# HzMF_Odrive.net
KiCad netlist of a schematic drawn in Altium Designer
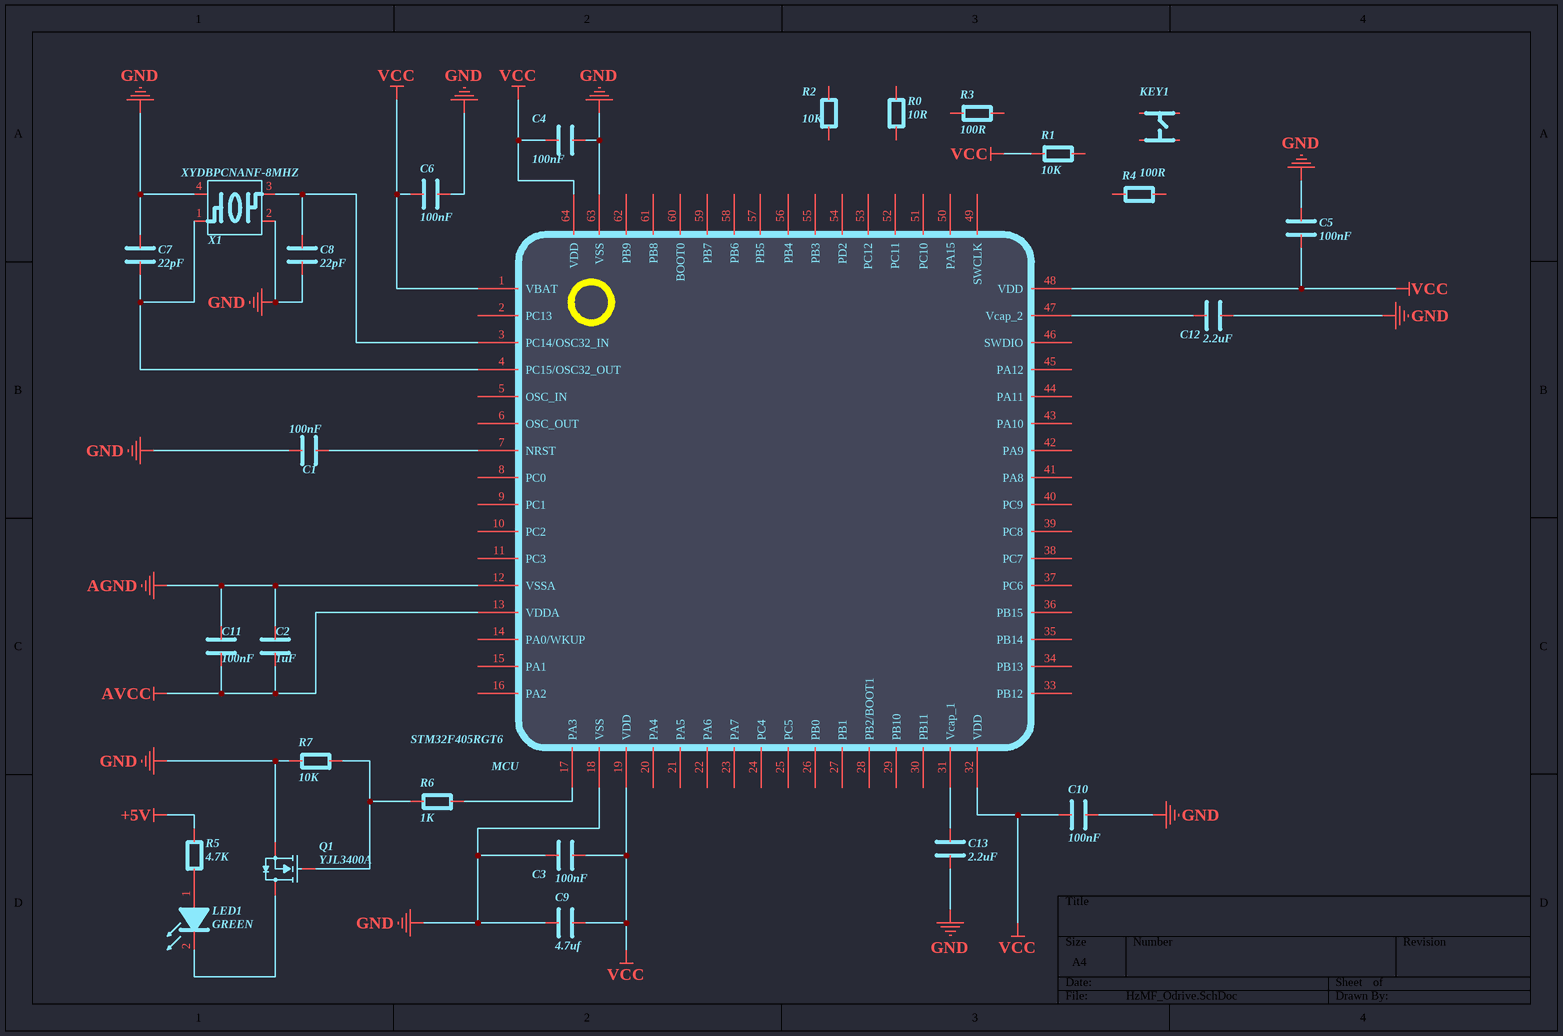
[diagram p0: HzMF_Odrive.SchDoc]

(export (version "E")
  (design (tool "Eeschema 10.0.6"))
  (components
    (comp (ref "C1")
      (value "100nF")
      (footprint "CAP_0603")
      (libsource (lib "HZMF_Private_Library") (part "C"))
    )
    (comp (ref "C2")
      (value "1uF")
      (footprint "CAP_0603")
      (description "电容")
      (libsource (lib "HZMF_Private_Library") (part "C"))
    )
    (comp (ref "C3")
      (value "100nF")
      (footprint "CAP_0603")
      (description "电容")
      (libsource (lib "HZMF_Private_Library") (part "C"))
    )
    (comp (ref "C4")
      (value "100nF")
      (footprint "CAP_0603")
      (description "电容")
      (libsource (lib "HZMF_Private_Library") (part "C"))
    )
    (comp (ref "C5")
      (value "100nF")
      (footprint "CAP_0603")
      (description "电容")
      (libsource (lib "HZMF_Private_Library") (part "C"))
    )
    (comp (ref "C6")
      (value "100nF")
      (footprint "CAP_0603")
      (description "电容")
      (libsource (lib "HZMF_Private_Library") (part "C"))
    )
    (comp (ref "C7")
      (value "22pF")
      (footprint "CAP_0603")
      (description "电容")
      (libsource (lib "HZMF_Private_Library") (part "C"))
    )
    (comp (ref "C8")
      (value "22pF")
      (footprint "CAP_0603")
      (description "电容")
      (libsource (lib "HZMF_Private_Library") (part "C"))
    )
    (comp (ref "C9")
      (value "4.7uf")
      (footprint "CAP_0603")
      (description "电容")
      (libsource (lib "HZMF_Private_Library") (part "C"))
    )
    (comp (ref "C10")
      (value "100nF")
      (footprint "CAP_0603")
      (description "电容")
      (libsource (lib "HZMF_Private_Library") (part "C"))
    )
    (comp (ref "C11")
      (value "100nF")
      (footprint "CAP_0603")
      (description "电容")
      (libsource (lib "HZMF_Private_Library") (part "C"))
    )
    (comp (ref "C12")
      (value "2.2uF")
      (footprint "CAP_0603")
      (description "电容")
      (libsource (lib "HZMF_Private_Library") (part "C"))
    )
    (comp (ref "C13")
      (value "2.2uF")
      (footprint "CAP_0603")
      (description "电容")
      (libsource (lib "HZMF_Private_Library") (part "C"))
    )
    (comp (ref "KEY1")
      (value "K1")
      (footprint "KEY-SMD_4P-L6.0-W6.0-P4.50-LS10.0")
      (description "Button")
      (libsource (lib "HZMF_Private_Library") (part "Button_4P"))
    )
    (comp (ref "LED1")
      (value "GREEN")
      (footprint "LED_green")
      (description "LED灯")
      (libsource (lib "HZMF_Private_Library") (part "LED"))
    )
    (comp (ref "MCU")
      (value "STM32F405RGT6")
      (footprint "LQFP_64")
      (description "STM32F4")
      (libsource (lib "HZMF_Private_Library") (part "STM32F405RGT6"))
    )
    (comp (ref "Q1")
      (value "YJL3400A")
      (footprint "SOT23_3")
      (description "N_MOS")
      (libsource (lib "HZMF_Private_Library") (part "MOSFET_N"))
    )
    (comp (ref "R0")
      (value "10R")
      (footprint "RES_0603")
      (description "电阻")
      (libsource (lib "HZMF_Private_Library") (part "R"))
    )
    (comp (ref "R1") (value "10K") (footprint "RES_0603") (libsource (lib "HZMF_Private_Library") (part "R")))
    (comp (ref "R2")
      (value "10K")
      (footprint "RES_0603")
      (description "电阻")
      (libsource (lib "HZMF_Private_Library") (part "R"))
    )
    (comp (ref "R3")
      (value "100R")
      (footprint "RES_0603")
      (description "电阻")
      (libsource (lib "HZMF_Private_Library") (part "R"))
    )
    (comp (ref "R4")
      (value "100R")
      (footprint "RES_0603")
      (description "电阻")
      (libsource (lib "HZMF_Private_Library") (part "R"))
    )
    (comp (ref "R5")
      (value "4.7K")
      (footprint "RES_0603")
      (description "电阻")
      (libsource (lib "HZMF_Private_Library") (part "R"))
    )
    (comp (ref "R6")
      (value "1K")
      (footprint "RES_0603")
      (description "电阻")
      (libsource (lib "HZMF_Private_Library") (part "R"))
    )
    (comp (ref "R7")
      (value "10K")
      (footprint "RES_0603")
      (description "电阻")
      (libsource (lib "HZMF_Private_Library") (part "R"))
    )
    (comp (ref "X1")
      (value "XYDBPCNANF-8MHZ")
      (footprint "CARSTAL_4P_2520")
      (description "四脚无源晶振")
      (fields
        (field (name "MANUFACTURER") "TAITIEN(泰艺电子)")
        (field (name "MANUFACTURER PART") "XYDBPCNANF-12MHZ")
      )
      (libsource (lib "HZMF_Private_Library") (part "Crystal_4P"))
    )
  )
  (nets
    (net (code "1") (name "+5V") (class "Default")
      (node (ref "R5") (pin "1") (pinfunction "1_1") (pintype "passive"))
    )
    (net (code "2") (name "AGND") (class "Default")
      (node (ref "C11") (pin "1") (pinfunction "1_1") (pintype "passive"))
      (node (ref "C2") (pin "1") (pinfunction "1_1") (pintype "passive"))
      (node (ref "MCU") (pin "12") (pinfunction "VSSA_12") (pintype "passive"))
    )
    (net (code "3") (name "AVCC") (class "Default")
      (node (ref "C11") (pin "2") (pinfunction "2_2") (pintype "passive"))
      (node (ref "C2") (pin "2") (pinfunction "2_2") (pintype "passive"))
      (node (ref "MCU") (pin "13") (pinfunction "VDDA_13") (pintype "passive"))
    )
    (net (code "4") (name "GND") (class "Default")
      (node (ref "C1") (pin "2") (pinfunction "2_2") (pintype "passive"))
      (node (ref "C10") (pin "1") (pinfunction "1_1") (pintype "passive"))
      (node (ref "C12") (pin "2") (pinfunction "2_2") (pintype "passive"))
      (node (ref "C13") (pin "2") (pinfunction "2_2") (pintype "passive"))
      (node (ref "C3") (pin "1") (pinfunction "1_1") (pintype "passive"))
      (node (ref "C4") (pin "2") (pinfunction "2_2") (pintype "passive"))
      (node (ref "C5") (pin "1") (pinfunction "1_1") (pintype "passive"))
      (node (ref "C6") (pin "1") (pinfunction "1_1") (pintype "passive"))
      (node (ref "C7") (pin "1") (pinfunction "1_1") (pintype "passive"))
      (node (ref "C8") (pin "2") (pinfunction "2_2") (pintype "passive"))
      (node (ref "C9") (pin "1") (pinfunction "1_1") (pintype "passive"))
      (node (ref "MCU") (pin "18") (pinfunction "VSS_18") (pintype "passive"))
      (node (ref "MCU") (pin "63") (pinfunction "VSS_63") (pintype "passive"))
      (node (ref "Q1") (pin "2") (pinfunction "S_2") (pintype "passive"))
      (node (ref "R7") (pin "1") (pinfunction "1_1") (pintype "passive"))
      (node (ref "X1") (pin "2") (pinfunction "GND_2") (pintype "passive"))
      (node (ref "X1") (pin "4") (pinfunction "GND_4") (pintype "passive"))
    )
    (net (code "5") (name "Net-(LED1-+)") (class "Default")
      (node (ref "LED1") (pin "1") (pinfunction "+_1") (pintype "passive"))
      (node (ref "R5") (pin "2") (pinfunction "2_2") (pintype "passive"))
    )
    (net (code "6") (name "Net-(LED1--)") (class "Default")
      (node (ref "LED1") (pin "2") (pinfunction "-_2") (pintype "passive"))
      (node (ref "Q1") (pin "3") (pinfunction "D_3") (pintype "passive"))
    )
    (net (code "7") (name "Net-(MCU-NRST)") (class "Default")
      (node (ref "C1") (pin "1") (pinfunction "1_1") (pintype "passive"))
      (node (ref "MCU") (pin "7") (pinfunction "NRST_7") (pintype "passive"))
    )
    (net (code "8") (name "Net-(MCU-PA3)") (class "Default")
      (node (ref "MCU") (pin "17") (pinfunction "PA3_17") (pintype "passive"))
      (node (ref "R6") (pin "2") (pinfunction "2_2") (pintype "passive"))
    )
    (net (code "9") (name "Net-(MCU-PC14{slash}OSC32_IN)") (class "Default")
      (node (ref "C8") (pin "1") (pinfunction "1_1") (pintype "passive"))
      (node (ref "MCU") (pin "3") (pinfunction "PC14/OSC32_IN_3") (pintype "passive"))
      (node (ref "X1") (pin "3") (pinfunction "3_3") (pintype "passive"))
    )
    (net (code "10") (name "Net-(MCU-PC15{slash}OSC32_OUT)") (class "Default")
      (node (ref "C7") (pin "2") (pinfunction "2_2") (pintype "passive"))
      (node (ref "MCU") (pin "4") (pinfunction "PC15/OSC32_OUT_4") (pintype "passive"))
      (node (ref "X1") (pin "1") (pinfunction "1_1") (pintype "passive"))
    )
    (net (code "11") (name "Net-(MCU-Vcap_1)") (class "Default")
      (node (ref "C13") (pin "1") (pinfunction "1_1") (pintype "passive"))
      (node (ref "MCU") (pin "31") (pinfunction "Vcap_1_31") (pintype "passive"))
    )
    (net (code "12") (name "Net-(MCU-Vcap_2)") (class "Default")
      (node (ref "C12") (pin "1") (pinfunction "1_1") (pintype "passive"))
      (node (ref "MCU") (pin "47") (pinfunction "Vcap_2_47") (pintype "passive"))
    )
    (net (code "13") (name "Net-(Q1-G)") (class "Default")
      (node (ref "Q1") (pin "1") (pinfunction "G_1") (pintype "passive"))
      (node (ref "R6") (pin "1") (pinfunction "1_1") (pintype "passive"))
      (node (ref "R7") (pin "2") (pinfunction "2_2") (pintype "passive"))
    )
    (net (code "14") (name "VCC") (class "Default")
      (node (ref "C10") (pin "2") (pinfunction "2_2") (pintype "passive"))
      (node (ref "C3") (pin "2") (pinfunction "2_2") (pintype "passive"))
      (node (ref "C4") (pin "1") (pinfunction "1_1") (pintype "passive"))
      (node (ref "C5") (pin "2") (pinfunction "2_2") (pintype "passive"))
      (node (ref "C6") (pin "2") (pinfunction "2_2") (pintype "passive"))
      (node (ref "C9") (pin "2") (pinfunction "2_2") (pintype "passive"))
      (node (ref "MCU") (pin "1") (pinfunction "VBAT_1") (pintype "passive"))
      (node (ref "MCU") (pin "19") (pinfunction "VDD_19") (pintype "passive"))
      (node (ref "MCU") (pin "32") (pinfunction "VDD_32") (pintype "passive"))
      (node (ref "MCU") (pin "48") (pinfunction "VDD_48") (pintype "passive"))
      (node (ref "MCU") (pin "64") (pinfunction "VDD_64") (pintype "passive"))
      (node (ref "R1") (pin "2") (pinfunction "2_2") (pintype "passive"))
    )
    (net (code "15") (name "unconnected-(KEY1-Pad1)") (class "Default")
      (node (ref "KEY1") (pin "1") (pinfunction "1_1") (pintype "passive"))
    )
    (net (code "16") (name "unconnected-(KEY1-Pad2)") (class "Default")
      (node (ref "KEY1") (pin "2") (pinfunction "2_2") (pintype "passive"))
    )
    (net (code "17") (name "unconnected-(KEY1-Pad3)") (class "Default")
      (node (ref "KEY1") (pin "3") (pinfunction "3_3") (pintype "passive"))
    )
    (net (code "18") (name "unconnected-(KEY1-Pad4)") (class "Default")
      (node (ref "KEY1") (pin "4") (pinfunction "4_4") (pintype "passive"))
    )
    (net (code "19") (name "unconnected-(MCU-BOOT0-Pad60)") (class "Default")
      (node (ref "MCU") (pin "60") (pinfunction "BOOT0_60") (pintype "passive"))
    )
    (net (code "20") (name "unconnected-(MCU-OSC_IN-Pad5)") (class "Default")
      (node (ref "MCU") (pin "5") (pinfunction "OSC_IN_5") (pintype "passive"))
    )
    (net (code "21") (name "unconnected-(MCU-OSC_OUT-Pad6)") (class "Default")
      (node (ref "MCU") (pin "6") (pinfunction "OSC_OUT_6") (pintype "passive"))
    )
    (net (code "22") (name "unconnected-(MCU-PA0{slash}WKUP-Pad14)") (class "Default")
      (node (ref "MCU") (pin "14") (pinfunction "PA0/WKUP_14") (pintype "passive"))
    )
    (net (code "23") (name "unconnected-(MCU-PA1-Pad15)") (class "Default")
      (node (ref "MCU") (pin "15") (pinfunction "PA1_15") (pintype "passive"))
    )
    (net (code "24") (name "unconnected-(MCU-PA2-Pad16)") (class "Default")
      (node (ref "MCU") (pin "16") (pinfunction "PA2_16") (pintype "passive"))
    )
    (net (code "25") (name "unconnected-(MCU-PA4-Pad20)") (class "Default")
      (node (ref "MCU") (pin "20") (pinfunction "PA4_20") (pintype "passive"))
    )
    (net (code "26") (name "unconnected-(MCU-PA5-Pad21)") (class "Default")
      (node (ref "MCU") (pin "21") (pinfunction "PA5_21") (pintype "passive"))
    )
    (net (code "27") (name "unconnected-(MCU-PA6-Pad22)") (class "Default")
      (node (ref "MCU") (pin "22") (pinfunction "PA6_22") (pintype "passive"))
    )
    (net (code "28") (name "unconnected-(MCU-PA7-Pad23)") (class "Default")
      (node (ref "MCU") (pin "23") (pinfunction "PA7_23") (pintype "passive"))
    )
    (net (code "29") (name "unconnected-(MCU-PA8-Pad41)") (class "Default")
      (node (ref "MCU") (pin "41") (pinfunction "PA8_41") (pintype "passive"))
    )
    (net (code "30") (name "unconnected-(MCU-PA9-Pad42)") (class "Default")
      (node (ref "MCU") (pin "42") (pinfunction "PA9_42") (pintype "passive"))
    )
    (net (code "31") (name "unconnected-(MCU-PA10-Pad43)") (class "Default")
      (node (ref "MCU") (pin "43") (pinfunction "PA10_43") (pintype "passive"))
    )
    (net (code "32") (name "unconnected-(MCU-PA11-Pad44)") (class "Default")
      (node (ref "MCU") (pin "44") (pinfunction "PA11_44") (pintype "passive"))
    )
    (net (code "33") (name "unconnected-(MCU-PA12-Pad45)") (class "Default")
      (node (ref "MCU") (pin "45") (pinfunction "PA12_45") (pintype "passive"))
    )
    (net (code "34") (name "unconnected-(MCU-PA15-Pad50)") (class "Default")
      (node (ref "MCU") (pin "50") (pinfunction "PA15_50") (pintype "passive"))
    )
    (net (code "35") (name "unconnected-(MCU-PB0-Pad26)") (class "Default")
      (node (ref "MCU") (pin "26") (pinfunction "PB0_26") (pintype "passive"))
    )
    (net (code "36") (name "unconnected-(MCU-PB1-Pad27)") (class "Default")
      (node (ref "MCU") (pin "27") (pinfunction "PB1_27") (pintype "passive"))
    )
    (net (code "37") (name "unconnected-(MCU-PB2{slash}BOOT1-Pad28)") (class "Default")
      (node (ref "MCU") (pin "28") (pinfunction "PB2/BOOT1_28") (pintype "passive"))
    )
    (net (code "38") (name "unconnected-(MCU-PB3-Pad55)") (class "Default")
      (node (ref "MCU") (pin "55") (pinfunction "PB3_55") (pintype "passive"))
    )
    (net (code "39") (name "unconnected-(MCU-PB4-Pad56)") (class "Default")
      (node (ref "MCU") (pin "56") (pinfunction "PB4_56") (pintype "passive"))
    )
    (net (code "40") (name "unconnected-(MCU-PB5-Pad57)") (class "Default")
      (node (ref "MCU") (pin "57") (pinfunction "PB5_57") (pintype "passive"))
    )
    (net (code "41") (name "unconnected-(MCU-PB6-Pad58)") (class "Default")
      (node (ref "MCU") (pin "58") (pinfunction "PB6_58") (pintype "passive"))
    )
    (net (code "42") (name "unconnected-(MCU-PB7-Pad59)") (class "Default")
      (node (ref "MCU") (pin "59") (pinfunction "PB7_59") (pintype "passive"))
    )
    (net (code "43") (name "unconnected-(MCU-PB8-Pad61)") (class "Default")
      (node (ref "MCU") (pin "61") (pinfunction "PB8_61") (pintype "passive"))
    )
    (net (code "44") (name "unconnected-(MCU-PB9-Pad62)") (class "Default")
      (node (ref "MCU") (pin "62") (pinfunction "PB9_62") (pintype "passive"))
    )
    (net (code "45") (name "unconnected-(MCU-PB10-Pad29)") (class "Default")
      (node (ref "MCU") (pin "29") (pinfunction "PB10_29") (pintype "passive"))
    )
    (net (code "46") (name "unconnected-(MCU-PB11-Pad30)") (class "Default")
      (node (ref "MCU") (pin "30") (pinfunction "PB11_30") (pintype "passive"))
    )
    (net (code "47") (name "unconnected-(MCU-PB12-Pad33)") (class "Default")
      (node (ref "MCU") (pin "33") (pinfunction "PB12_33") (pintype "passive"))
    )
    (net (code "48") (name "unconnected-(MCU-PB13-Pad34)") (class "Default")
      (node (ref "MCU") (pin "34") (pinfunction "PB13_34") (pintype "passive"))
    )
    (net (code "49") (name "unconnected-(MCU-PB14-Pad35)") (class "Default")
      (node (ref "MCU") (pin "35") (pinfunction "PB14_35") (pintype "passive"))
    )
    (net (code "50") (name "unconnected-(MCU-PB15-Pad36)") (class "Default")
      (node (ref "MCU") (pin "36") (pinfunction "PB15_36") (pintype "passive"))
    )
    (net (code "51") (name "unconnected-(MCU-PC0-Pad8)") (class "Default")
      (node (ref "MCU") (pin "8") (pinfunction "PC0_8") (pintype "passive"))
    )
    (net (code "52") (name "unconnected-(MCU-PC1-Pad9)") (class "Default")
      (node (ref "MCU") (pin "9") (pinfunction "PC1_9") (pintype "passive"))
    )
    (net (code "53") (name "unconnected-(MCU-PC2-Pad10)") (class "Default")
      (node (ref "MCU") (pin "10") (pinfunction "PC2_10") (pintype "passive"))
    )
    (net (code "54") (name "unconnected-(MCU-PC3-Pad11)") (class "Default")
      (node (ref "MCU") (pin "11") (pinfunction "PC3_11") (pintype "passive"))
    )
    (net (code "55") (name "unconnected-(MCU-PC4-Pad24)") (class "Default")
      (node (ref "MCU") (pin "24") (pinfunction "PC4_24") (pintype "passive"))
    )
    (net (code "56") (name "unconnected-(MCU-PC5-Pad25)") (class "Default")
      (node (ref "MCU") (pin "25") (pinfunction "PC5_25") (pintype "passive"))
    )
    (net (code "57") (name "unconnected-(MCU-PC6-Pad37)") (class "Default")
      (node (ref "MCU") (pin "37") (pinfunction "PC6_37") (pintype "passive"))
    )
    (net (code "58") (name "unconnected-(MCU-PC7-Pad38)") (class "Default")
      (node (ref "MCU") (pin "38") (pinfunction "PC7_38") (pintype "passive"))
    )
    (net (code "59") (name "unconnected-(MCU-PC8-Pad39)") (class "Default")
      (node (ref "MCU") (pin "39") (pinfunction "PC8_39") (pintype "passive"))
    )
    (net (code "60") (name "unconnected-(MCU-PC9-Pad40)") (class "Default")
      (node (ref "MCU") (pin "40") (pinfunction "PC9_40") (pintype "passive"))
    )
    (net (code "61") (name "unconnected-(MCU-PC10-Pad51)") (class "Default")
      (node (ref "MCU") (pin "51") (pinfunction "PC10_51") (pintype "passive"))
    )
    (net (code "62") (name "unconnected-(MCU-PC11-Pad52)") (class "Default")
      (node (ref "MCU") (pin "52") (pinfunction "PC11_52") (pintype "passive"))
    )
    (net (code "63") (name "unconnected-(MCU-PC12-Pad53)") (class "Default")
      (node (ref "MCU") (pin "53") (pinfunction "PC12_53") (pintype "passive"))
    )
    (net (code "64") (name "unconnected-(MCU-PC13-Pad2)") (class "Default")
      (node (ref "MCU") (pin "2") (pinfunction "PC13_2") (pintype "passive"))
    )
    (net (code "65") (name "unconnected-(MCU-PD2-Pad54)") (class "Default")
      (node (ref "MCU") (pin "54") (pinfunction "PD2_54") (pintype "passive"))
    )
    (net (code "66") (name "unconnected-(MCU-SWCLK-Pad49)") (class "Default")
      (node (ref "MCU") (pin "49") (pinfunction "SWCLK_49") (pintype "passive"))
    )
    (net (code "67") (name "unconnected-(MCU-SWDIO-Pad46)") (class "Default")
      (node (ref "MCU") (pin "46") (pinfunction "SWDIO_46") (pintype "passive"))
    )
    (net (code "68") (name "unconnected-(R0-Pad1)") (class "Default")
      (node (ref "R0") (pin "1") (pinfunction "1_1") (pintype "passive"))
    )
    (net (code "69") (name "unconnected-(R0-Pad2)") (class "Default")
      (node (ref "R0") (pin "2") (pinfunction "2_2") (pintype "passive"))
    )
    (net (code "70") (name "unconnected-(R1-Pad1)") (class "Default")
      (node (ref "R1") (pin "1") (pinfunction "1_1") (pintype "passive"))
    )
    (net (code "71") (name "unconnected-(R2-Pad1)") (class "Default")
      (node (ref "R2") (pin "1") (pinfunction "1_1") (pintype "passive"))
    )
    (net (code "72") (name "unconnected-(R2-Pad2)") (class "Default")
      (node (ref "R2") (pin "2") (pinfunction "2_2") (pintype "passive"))
    )
    (net (code "73") (name "unconnected-(R3-Pad1)") (class "Default")
      (node (ref "R3") (pin "1") (pinfunction "1_1") (pintype "passive"))
    )
    (net (code "74") (name "unconnected-(R3-Pad2)") (class "Default")
      (node (ref "R3") (pin "2") (pinfunction "2_2") (pintype "passive"))
    )
    (net (code "75") (name "unconnected-(R4-Pad1)") (class "Default")
      (node (ref "R4") (pin "1") (pinfunction "1_1") (pintype "passive"))
    )
    (net (code "76") (name "unconnected-(R4-Pad2)") (class "Default")
      (node (ref "R4") (pin "2") (pinfunction "2_2") (pintype "passive"))
    )
  )
)
